# cpld.net
KiCad netlist of a schematic drawn in Altium Designer
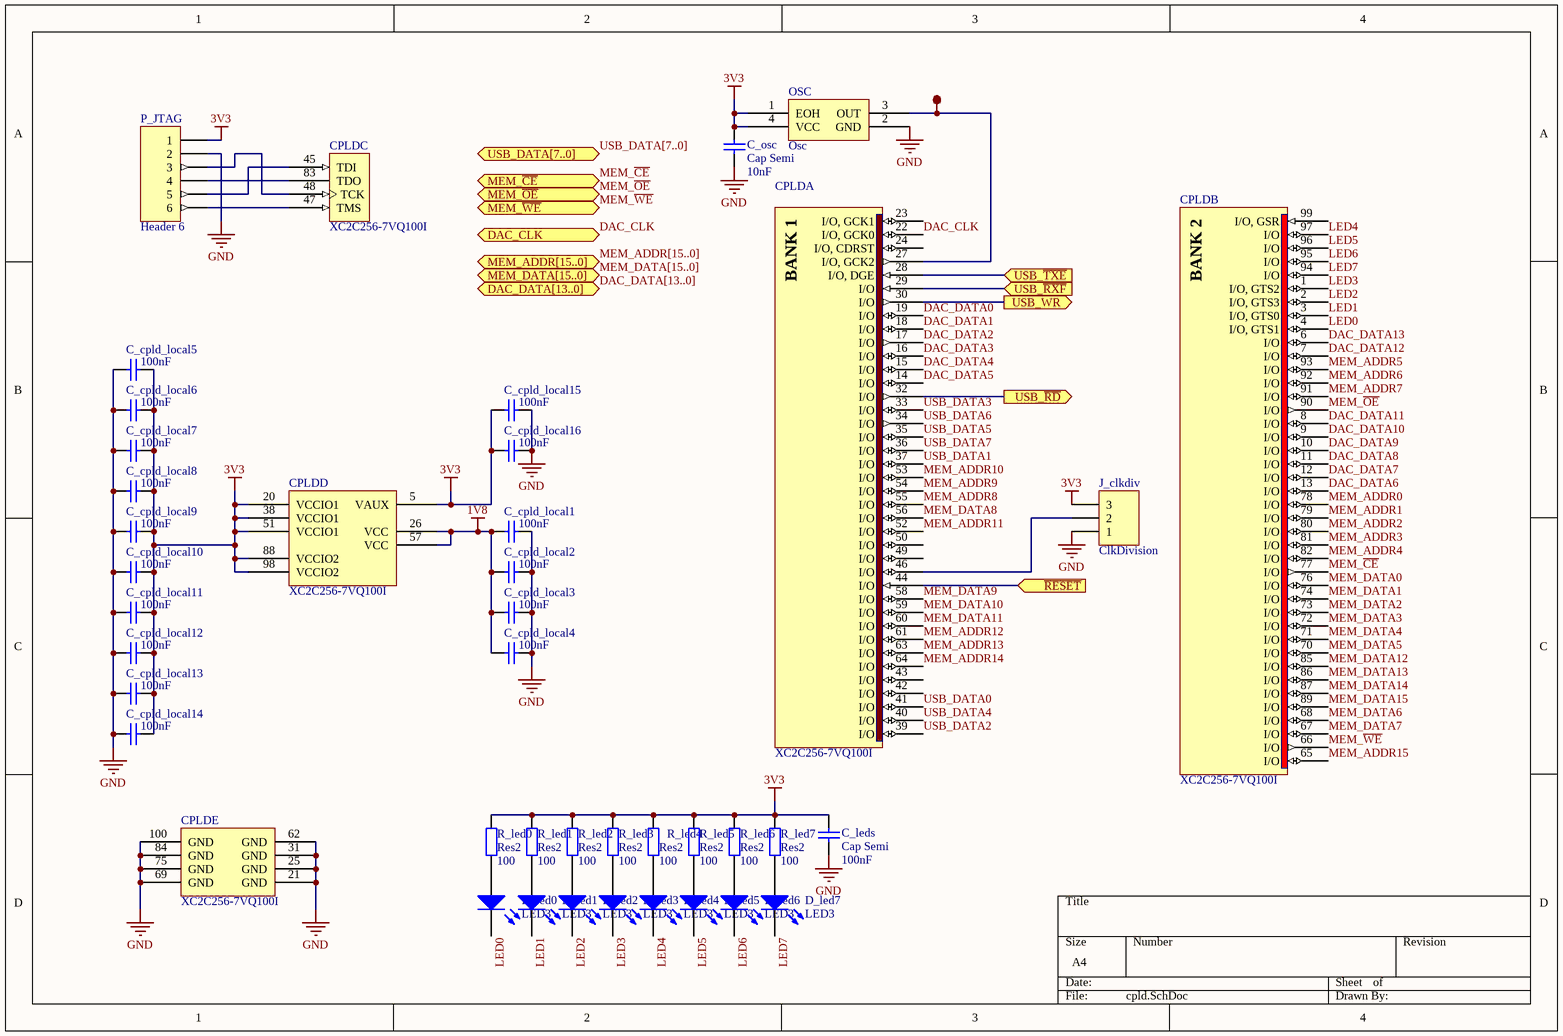
[diagram p0: cpld.SchDoc]

(export (version "E")
  (design (tool "Eeschema 10.0.6"))
  (components
    (comp (ref "CPLD")
      (value "XC2C256-7VQ100I")
      (footprint "VQ100_N")
      (description "CoolRunner-II 1.8V, 256 Macrocell CPLD, 80 User I/Os, 100-Pin VQFP, Industrial Grade")
      (fields (field (name "PUBLISHER") "Altium Limited"))
      (libsource (lib "Xilinx CoolRunner II") (part "XC2C256-7VQ100I"))
    )
    (comp (ref "C_cpld_local1")
      (value "100nF")
      (footprint "ourprints:0805")
      (description "Capacitor (Semiconductor SIM Model)")
      (fields (field (name "Comment") "Cap Semi") (field (name "PUBLISHER") "Altium Limited"))
      (libsource (lib "Miscellaneous Devices") (part "Cap Semi"))
    )
    (comp (ref "C_cpld_local2")
      (value "100nF")
      (footprint "ourprints:0805")
      (description "Capacitor (Semiconductor SIM Model)")
      (fields (field (name "Comment") "Cap Semi") (field (name "PUBLISHER") "Altium Limited"))
      (libsource (lib "Miscellaneous Devices") (part "Cap Semi"))
    )
    (comp (ref "C_cpld_local3")
      (value "100nF")
      (footprint "ourprints:0805")
      (description "Capacitor (Semiconductor SIM Model)")
      (fields (field (name "Comment") "Cap Semi") (field (name "PUBLISHER") "Altium Limited"))
      (libsource (lib "Miscellaneous Devices") (part "Cap Semi"))
    )
    (comp (ref "C_cpld_local4")
      (value "100nF")
      (footprint "ourprints:0805")
      (description "Capacitor (Semiconductor SIM Model)")
      (fields (field (name "Comment") "Cap Semi") (field (name "PUBLISHER") "Altium Limited"))
      (libsource (lib "Miscellaneous Devices") (part "Cap Semi"))
    )
    (comp (ref "C_cpld_local5")
      (value "100nF")
      (footprint "ourprints:0805")
      (description "Capacitor (Semiconductor SIM Model)")
      (fields (field (name "Comment") "Cap Semi") (field (name "PUBLISHER") "Altium Limited"))
      (libsource (lib "Miscellaneous Devices") (part "Cap Semi"))
    )
    (comp (ref "C_cpld_local6")
      (value "100nF")
      (footprint "ourprints:0805")
      (description "Capacitor (Semiconductor SIM Model)")
      (fields (field (name "Comment") "Cap Semi") (field (name "PUBLISHER") "Altium Limited"))
      (libsource (lib "Miscellaneous Devices") (part "Cap Semi"))
    )
    (comp (ref "C_cpld_local7")
      (value "100nF")
      (footprint "ourprints:0805")
      (description "Capacitor (Semiconductor SIM Model)")
      (fields (field (name "Comment") "Cap Semi") (field (name "PUBLISHER") "Altium Limited"))
      (libsource (lib "Miscellaneous Devices") (part "Cap Semi"))
    )
    (comp (ref "C_cpld_local8")
      (value "100nF")
      (footprint "ourprints:0805")
      (description "Capacitor (Semiconductor SIM Model)")
      (fields (field (name "Comment") "Cap Semi") (field (name "PUBLISHER") "Altium Limited"))
      (libsource (lib "Miscellaneous Devices") (part "Cap Semi"))
    )
    (comp (ref "C_cpld_local9")
      (value "100nF")
      (footprint "ourprints:0805")
      (description "Capacitor (Semiconductor SIM Model)")
      (fields (field (name "Comment") "Cap Semi") (field (name "PUBLISHER") "Altium Limited"))
      (libsource (lib "Miscellaneous Devices") (part "Cap Semi"))
    )
    (comp (ref "C_cpld_local10")
      (value "100nF")
      (footprint "ourprints:0805")
      (description "Capacitor (Semiconductor SIM Model)")
      (fields (field (name "Comment") "Cap Semi") (field (name "PUBLISHER") "Altium Limited"))
      (libsource (lib "Miscellaneous Devices") (part "Cap Semi"))
    )
    (comp (ref "C_cpld_local11")
      (value "100nF")
      (footprint "ourprints:0805")
      (description "Capacitor (Semiconductor SIM Model)")
      (fields (field (name "Comment") "Cap Semi") (field (name "PUBLISHER") "Altium Limited"))
      (libsource (lib "Miscellaneous Devices") (part "Cap Semi"))
    )
    (comp (ref "C_cpld_local12")
      (value "100nF")
      (footprint "ourprints:0805")
      (description "Capacitor (Semiconductor SIM Model)")
      (fields (field (name "Comment") "Cap Semi") (field (name "PUBLISHER") "Altium Limited"))
      (libsource (lib "Miscellaneous Devices") (part "Cap Semi"))
    )
    (comp (ref "C_cpld_local13")
      (value "100nF")
      (footprint "ourprints:0805")
      (description "Capacitor (Semiconductor SIM Model)")
      (fields (field (name "Comment") "Cap Semi") (field (name "PUBLISHER") "Altium Limited"))
      (libsource (lib "Miscellaneous Devices") (part "Cap Semi"))
    )
    (comp (ref "C_cpld_local14")
      (value "100nF")
      (footprint "ourprints:0805")
      (description "Capacitor (Semiconductor SIM Model)")
      (fields (field (name "Comment") "Cap Semi") (field (name "PUBLISHER") "Altium Limited"))
      (libsource (lib "Miscellaneous Devices") (part "Cap Semi"))
    )
    (comp (ref "C_cpld_local15")
      (value "100nF")
      (footprint "ourprints:0805")
      (description "Capacitor (Semiconductor SIM Model)")
      (fields (field (name "Comment") "Cap Semi") (field (name "PUBLISHER") "Altium Limited"))
      (libsource (lib "Miscellaneous Devices") (part "Cap Semi"))
    )
    (comp (ref "C_cpld_local16")
      (value "100nF")
      (footprint "ourprints:0805")
      (description "Capacitor (Semiconductor SIM Model)")
      (fields (field (name "Comment") "Cap Semi") (field (name "PUBLISHER") "Altium Limited"))
      (libsource (lib "Miscellaneous Devices") (part "Cap Semi"))
    )
    (comp (ref "C_leds")
      (value "Cap Semi")
      (footprint "ourprints:0805")
      (description "Capacitor (Semiconductor SIM Model)")
      (fields (field (name "ALTIUM_VALUE") "100nF") (field (name "PUBLISHER") "Altium Limited"))
      (libsource (lib "Miscellaneous Devices") (part "Cap Semi"))
    )
    (comp (ref "C_osc")
      (value "Cap Semi")
      (footprint "ourprints:0805")
      (description "Capacitor (Semiconductor SIM Model)")
      (fields (field (name "ALTIUM_VALUE") "10nF") (field (name "PUBLISHER") "Altium Limited"))
      (libsource (lib "Miscellaneous Devices") (part "Cap Semi"))
    )
    (comp (ref "D_led0")
      (value "LED3")
      (footprint "ourprints:0805")
      (description "Typical BLUE SiC LED")
      (fields (field (name "PUBLISHER") "Altium Limited"))
      (libsource (lib "Miscellaneous Devices") (part "LED3"))
    )
    (comp (ref "D_led1")
      (value "LED3")
      (footprint "ourprints:0805")
      (description "Typical BLUE SiC LED")
      (fields (field (name "PUBLISHER") "Altium Limited"))
      (libsource (lib "Miscellaneous Devices") (part "LED3"))
    )
    (comp (ref "D_led2")
      (value "LED3")
      (footprint "ourprints:0805")
      (description "Typical BLUE SiC LED")
      (fields (field (name "PUBLISHER") "Altium Limited"))
      (libsource (lib "Miscellaneous Devices") (part "LED3"))
    )
    (comp (ref "D_led3")
      (value "LED3")
      (footprint "ourprints:0805")
      (description "Typical BLUE SiC LED")
      (fields (field (name "PUBLISHER") "Altium Limited"))
      (libsource (lib "Miscellaneous Devices") (part "LED3"))
    )
    (comp (ref "D_led4")
      (value "LED3")
      (footprint "ourprints:0805")
      (description "Typical BLUE SiC LED")
      (fields (field (name "PUBLISHER") "Altium Limited"))
      (libsource (lib "Miscellaneous Devices") (part "LED3"))
    )
    (comp (ref "D_led5")
      (value "LED3")
      (footprint "ourprints:0805")
      (description "Typical BLUE SiC LED")
      (fields (field (name "PUBLISHER") "Altium Limited"))
      (libsource (lib "Miscellaneous Devices") (part "LED3"))
    )
    (comp (ref "D_led6")
      (value "LED3")
      (footprint "ourprints:0805")
      (description "Typical BLUE SiC LED")
      (fields (field (name "PUBLISHER") "Altium Limited"))
      (libsource (lib "Miscellaneous Devices") (part "LED3"))
    )
    (comp (ref "D_led7")
      (value "LED3")
      (footprint "ourprints:0805")
      (description "Typical BLUE SiC LED")
      (fields (field (name "PUBLISHER") "Altium Limited"))
      (libsource (lib "Miscellaneous Devices") (part "LED3"))
    )
    (comp (ref "J_clkdiv")
      (value "ClkDivision")
      (footprint "HDR1X3")
      (description "Header, 3-Pin")
      (fields (field (name "PUBLISHER") "Altium Limited"))
      (libsource (lib "Miscellaneous Connectors") (part "Header 3"))
    )
    (comp (ref "OSC") (value "Osc") (footprint "OSC") (libsource (lib "ourlibs") (part "Osc")))
    (comp (ref "P_JTAG")
      (value "Header 6")
      (footprint "HDR1X6")
      (description "Header, 6-Pin")
      (fields (field (name "PUBLISHER") "Altium Limited"))
      (libsource (lib "Miscellaneous Connectors") (part "Header 6"))
    )
    (comp (ref "R_led0")
      (value "Res2")
      (footprint "ourprints:0805")
      (description "Resistor")
      (fields (field (name "ALTIUM_VALUE") "100") (field (name "PUBLISHER") "Altium Limited"))
      (libsource (lib "Miscellaneous Devices") (part "Res2"))
    )
    (comp (ref "R_led1")
      (value "Res2")
      (footprint "ourprints:0805")
      (description "Resistor")
      (fields (field (name "ALTIUM_VALUE") "100") (field (name "PUBLISHER") "Altium Limited"))
      (libsource (lib "Miscellaneous Devices") (part "Res2"))
    )
    (comp (ref "R_led2")
      (value "Res2")
      (footprint "ourprints:0805")
      (description "Resistor")
      (fields (field (name "ALTIUM_VALUE") "100") (field (name "PUBLISHER") "Altium Limited"))
      (libsource (lib "Miscellaneous Devices") (part "Res2"))
    )
    (comp (ref "R_led3")
      (value "Res2")
      (footprint "ourprints:0805")
      (description "Resistor")
      (fields (field (name "ALTIUM_VALUE") "100") (field (name "PUBLISHER") "Altium Limited"))
      (libsource (lib "Miscellaneous Devices") (part "Res2"))
    )
    (comp (ref "R_led4")
      (value "Res2")
      (footprint "ourprints:0805")
      (description "Resistor")
      (fields (field (name "ALTIUM_VALUE") "100") (field (name "PUBLISHER") "Altium Limited"))
      (libsource (lib "Miscellaneous Devices") (part "Res2"))
    )
    (comp (ref "R_led5")
      (value "Res2")
      (footprint "ourprints:0805")
      (description "Resistor")
      (fields (field (name "ALTIUM_VALUE") "100") (field (name "PUBLISHER") "Altium Limited"))
      (libsource (lib "Miscellaneous Devices") (part "Res2"))
    )
    (comp (ref "R_led6")
      (value "Res2")
      (footprint "ourprints:0805")
      (description "Resistor")
      (fields (field (name "ALTIUM_VALUE") "100") (field (name "PUBLISHER") "Altium Limited"))
      (libsource (lib "Miscellaneous Devices") (part "Res2"))
    )
    (comp (ref "R_led7")
      (value "Res2")
      (footprint "ourprints:0805")
      (description "Resistor")
      (fields (field (name "ALTIUM_VALUE") "100") (field (name "PUBLISHER") "Altium Limited"))
      (libsource (lib "Miscellaneous Devices") (part "Res2"))
    )
    (comp (ref "TP_osc")
      (value "TestPoint")
      (footprint "testpoint")
      (libsource (lib "ourlibs") (part "TestPoint"))
    )
  )
  (nets
    (net (code "1") (name "/DAC_CLK") (class "Default")
      (node (ref "CPLD") (pin "22") (pinfunction "I/O,_GCK0_22") (pintype "bidirectional"))
    )
    (net (code "2") (name "/DAC_DATA0") (class "Default")
      (node (ref "CPLD") (pin "19") (pinfunction "I/O_19") (pintype "bidirectional"))
    )
    (net (code "3") (name "/DAC_DATA1") (class "Default")
      (node (ref "CPLD") (pin "18") (pinfunction "I/O_18") (pintype "bidirectional"))
    )
    (net (code "4") (name "/DAC_DATA2") (class "Default")
      (node (ref "CPLD") (pin "17") (pinfunction "I/O_17") (pintype "bidirectional"))
    )
    (net (code "5") (name "/DAC_DATA3") (class "Default")
      (node (ref "CPLD") (pin "16") (pinfunction "I/O_16") (pintype "bidirectional"))
    )
    (net (code "6") (name "/DAC_DATA4") (class "Default")
      (node (ref "CPLD") (pin "15") (pinfunction "I/O_15") (pintype "bidirectional"))
    )
    (net (code "7") (name "/DAC_DATA5") (class "Default")
      (node (ref "CPLD") (pin "14") (pinfunction "I/O_14") (pintype "bidirectional"))
    )
    (net (code "8") (name "/DAC_DATA6") (class "Default")
      (node (ref "CPLD") (pin "13") (pinfunction "I/O_13") (pintype "bidirectional"))
    )
    (net (code "9") (name "/DAC_DATA7") (class "Default")
      (node (ref "CPLD") (pin "12") (pinfunction "I/O_12") (pintype "bidirectional"))
    )
    (net (code "10") (name "/DAC_DATA8") (class "Default")
      (node (ref "CPLD") (pin "11") (pinfunction "I/O_11") (pintype "bidirectional"))
    )
    (net (code "11") (name "/DAC_DATA9") (class "Default")
      (node (ref "CPLD") (pin "10") (pinfunction "I/O_10") (pintype "bidirectional"))
    )
    (net (code "12") (name "/DAC_DATA10") (class "Default")
      (node (ref "CPLD") (pin "9") (pinfunction "I/O_9") (pintype "bidirectional"))
    )
    (net (code "13") (name "/DAC_DATA11") (class "Default")
      (node (ref "CPLD") (pin "8") (pinfunction "I/O_8") (pintype "bidirectional"))
    )
    (net (code "14") (name "/DAC_DATA12") (class "Default")
      (node (ref "CPLD") (pin "7") (pinfunction "I/O_7") (pintype "bidirectional"))
    )
    (net (code "15") (name "/DAC_DATA13") (class "Default")
      (node (ref "CPLD") (pin "6") (pinfunction "I/O_6") (pintype "bidirectional"))
    )
    (net (code "17") (name "/LED0") (class "Default")
      (node (ref "CPLD") (pin "4") (pinfunction "I/O,_GTS1_4") (pintype "bidirectional"))
      (node (ref "D_led0") (pin "2") (pinfunction "K_2") (pintype "passive"))
    )
    (net (code "18") (name "/LED1") (class "Default")
      (node (ref "CPLD") (pin "3") (pinfunction "I/O,_GTS0_3") (pintype "bidirectional"))
      (node (ref "D_led1") (pin "2") (pinfunction "K_2") (pintype "passive"))
    )
    (net (code "19") (name "/LED2") (class "Default")
      (node (ref "CPLD") (pin "2") (pinfunction "I/O,_GTS3_2") (pintype "bidirectional"))
      (node (ref "D_led2") (pin "2") (pinfunction "K_2") (pintype "passive"))
    )
    (net (code "20") (name "/LED3") (class "Default")
      (node (ref "CPLD") (pin "1") (pinfunction "I/O,_GTS2_1") (pintype "bidirectional"))
      (node (ref "D_led3") (pin "2") (pinfunction "K_2") (pintype "passive"))
    )
    (net (code "21") (name "/LED4") (class "Default")
      (node (ref "CPLD") (pin "97") (pinfunction "I/O_97") (pintype "bidirectional"))
      (node (ref "D_led4") (pin "2") (pinfunction "K_2") (pintype "passive"))
    )
    (net (code "22") (name "/LED5") (class "Default")
      (node (ref "CPLD") (pin "96") (pinfunction "I/O_96") (pintype "bidirectional"))
      (node (ref "D_led5") (pin "2") (pinfunction "K_2") (pintype "passive"))
    )
    (net (code "23") (name "/LED6") (class "Default")
      (node (ref "CPLD") (pin "95") (pinfunction "I/O_95") (pintype "bidirectional"))
      (node (ref "D_led6") (pin "2") (pinfunction "K_2") (pintype "passive"))
    )
    (net (code "24") (name "/LED7") (class "Default")
      (node (ref "CPLD") (pin "94") (pinfunction "I/O_94") (pintype "bidirectional"))
      (node (ref "D_led7") (pin "2") (pinfunction "K_2") (pintype "passive"))
    )
    (net (code "25") (name "/MEM_ADDR0") (class "Default")
      (node (ref "CPLD") (pin "78") (pinfunction "I/O_78") (pintype "bidirectional"))
    )
    (net (code "26") (name "/MEM_ADDR1") (class "Default")
      (node (ref "CPLD") (pin "79") (pinfunction "I/O_79") (pintype "bidirectional"))
    )
    (net (code "27") (name "/MEM_ADDR2") (class "Default")
      (node (ref "CPLD") (pin "80") (pinfunction "I/O_80") (pintype "bidirectional"))
    )
    (net (code "28") (name "/MEM_ADDR3") (class "Default")
      (node (ref "CPLD") (pin "81") (pinfunction "I/O_81") (pintype "bidirectional"))
    )
    (net (code "29") (name "/MEM_ADDR4") (class "Default")
      (node (ref "CPLD") (pin "82") (pinfunction "I/O_82") (pintype "bidirectional"))
    )
    (net (code "30") (name "/MEM_ADDR5") (class "Default")
      (node (ref "CPLD") (pin "93") (pinfunction "I/O_93") (pintype "bidirectional"))
    )
    (net (code "31") (name "/MEM_ADDR6") (class "Default")
      (node (ref "CPLD") (pin "92") (pinfunction "I/O_92") (pintype "bidirectional"))
    )
    (net (code "32") (name "/MEM_ADDR7") (class "Default")
      (node (ref "CPLD") (pin "91") (pinfunction "I/O_91") (pintype "bidirectional"))
    )
    (net (code "33") (name "/MEM_ADDR8") (class "Default")
      (node (ref "CPLD") (pin "55") (pinfunction "I/O_55") (pintype "bidirectional"))
    )
    (net (code "34") (name "/MEM_ADDR9") (class "Default")
      (node (ref "CPLD") (pin "54") (pinfunction "I/O_54") (pintype "bidirectional"))
    )
    (net (code "35") (name "/MEM_ADDR10") (class "Default")
      (node (ref "CPLD") (pin "53") (pinfunction "I/O_53") (pintype "bidirectional"))
    )
    (net (code "36") (name "/MEM_ADDR11") (class "Default")
      (node (ref "CPLD") (pin "52") (pinfunction "I/O_52") (pintype "bidirectional"))
    )
    (net (code "37") (name "/MEM_ADDR12") (class "Default")
      (node (ref "CPLD") (pin "61") (pinfunction "I/O_61") (pintype "bidirectional"))
    )
    (net (code "38") (name "/MEM_ADDR13") (class "Default")
      (node (ref "CPLD") (pin "63") (pinfunction "I/O_63") (pintype "bidirectional"))
    )
    (net (code "39") (name "/MEM_ADDR14") (class "Default")
      (node (ref "CPLD") (pin "64") (pinfunction "I/O_64") (pintype "bidirectional"))
    )
    (net (code "40") (name "/MEM_ADDR15") (class "Default")
      (node (ref "CPLD") (pin "65") (pinfunction "I/O_65") (pintype "bidirectional"))
    )
    (net (code "42") (name "/MEM_DATA0") (class "Default")
      (node (ref "CPLD") (pin "76") (pinfunction "I/O_76") (pintype "bidirectional"))
    )
    (net (code "43") (name "/MEM_DATA1") (class "Default")
      (node (ref "CPLD") (pin "74") (pinfunction "I/O_74") (pintype "bidirectional"))
    )
    (net (code "44") (name "/MEM_DATA2") (class "Default")
      (node (ref "CPLD") (pin "73") (pinfunction "I/O_73") (pintype "bidirectional"))
    )
    (net (code "45") (name "/MEM_DATA3") (class "Default")
      (node (ref "CPLD") (pin "72") (pinfunction "I/O_72") (pintype "bidirectional"))
    )
    (net (code "46") (name "/MEM_DATA4") (class "Default")
      (node (ref "CPLD") (pin "71") (pinfunction "I/O_71") (pintype "bidirectional"))
    )
    (net (code "47") (name "/MEM_DATA5") (class "Default")
      (node (ref "CPLD") (pin "70") (pinfunction "I/O_70") (pintype "bidirectional"))
    )
    (net (code "48") (name "/MEM_DATA6") (class "Default")
      (node (ref "CPLD") (pin "68") (pinfunction "I/O_68") (pintype "bidirectional"))
    )
    (net (code "49") (name "/MEM_DATA7") (class "Default")
      (node (ref "CPLD") (pin "67") (pinfunction "I/O_67") (pintype "bidirectional"))
    )
    (net (code "50") (name "/MEM_DATA8") (class "Default")
      (node (ref "CPLD") (pin "56") (pinfunction "I/O_56") (pintype "bidirectional"))
    )
    (net (code "51") (name "/MEM_DATA9") (class "Default")
      (node (ref "CPLD") (pin "58") (pinfunction "I/O_58") (pintype "bidirectional"))
    )
    (net (code "52") (name "/MEM_DATA10") (class "Default")
      (node (ref "CPLD") (pin "59") (pinfunction "I/O_59") (pintype "bidirectional"))
    )
    (net (code "53") (name "/MEM_DATA11") (class "Default")
      (node (ref "CPLD") (pin "60") (pinfunction "I/O_60") (pintype "bidirectional"))
    )
    (net (code "54") (name "/MEM_DATA12") (class "Default")
      (node (ref "CPLD") (pin "85") (pinfunction "I/O_85") (pintype "bidirectional"))
    )
    (net (code "55") (name "/MEM_DATA13") (class "Default")
      (node (ref "CPLD") (pin "86") (pinfunction "I/O_86") (pintype "bidirectional"))
    )
    (net (code "56") (name "/MEM_DATA14") (class "Default")
      (node (ref "CPLD") (pin "87") (pinfunction "I/O_87") (pintype "bidirectional"))
    )
    (net (code "57") (name "/MEM_DATA15") (class "Default")
      (node (ref "CPLD") (pin "89") (pinfunction "I/O_89") (pintype "bidirectional"))
    )
    (net (code "59") (name "/MEM_~{CE}") (class "Default")
      (node (ref "CPLD") (pin "77") (pinfunction "I/O_77") (pintype "bidirectional"))
    )
    (net (code "60") (name "/MEM_~{OE}") (class "Default")
      (node (ref "CPLD") (pin "90") (pinfunction "I/O_90") (pintype "bidirectional"))
    )
    (net (code "61") (name "/MEM_~{WE}") (class "Default")
      (node (ref "CPLD") (pin "66") (pinfunction "I/O_66") (pintype "bidirectional"))
    )
    (net (code "62") (name "/USB_DATA0") (class "Default")
      (node (ref "CPLD") (pin "41") (pinfunction "I/O_41") (pintype "bidirectional"))
    )
    (net (code "63") (name "/USB_DATA1") (class "Default")
      (node (ref "CPLD") (pin "37") (pinfunction "I/O_37") (pintype "bidirectional"))
    )
    (net (code "64") (name "/USB_DATA2") (class "Default")
      (node (ref "CPLD") (pin "39") (pinfunction "I/O_39") (pintype "bidirectional"))
    )
    (net (code "65") (name "/USB_DATA3") (class "Default")
      (node (ref "CPLD") (pin "33") (pinfunction "I/O_33") (pintype "bidirectional"))
    )
    (net (code "66") (name "/USB_DATA4") (class "Default")
      (node (ref "CPLD") (pin "40") (pinfunction "I/O_40") (pintype "bidirectional"))
    )
    (net (code "67") (name "/USB_DATA5") (class "Default")
      (node (ref "CPLD") (pin "35") (pinfunction "I/O_35") (pintype "bidirectional"))
    )
    (net (code "68") (name "/USB_DATA6") (class "Default")
      (node (ref "CPLD") (pin "34") (pinfunction "I/O_34") (pintype "bidirectional"))
    )
    (net (code "69") (name "/USB_DATA7") (class "Default")
      (node (ref "CPLD") (pin "36") (pinfunction "I/O_36") (pintype "bidirectional"))
    )
    (net (code "71") (name "/USB_WR") (class "Default")
      (node (ref "CPLD") (pin "30") (pinfunction "I/O_30") (pintype "bidirectional"))
    )
    (net (code "72") (name "/USB_~{RD}") (class "Default")
      (node (ref "CPLD") (pin "32") (pinfunction "I/O_32") (pintype "bidirectional"))
    )
    (net (code "73") (name "/USB_~{RXF}") (class "Default")
      (node (ref "CPLD") (pin "29") (pinfunction "I/O_29") (pintype "bidirectional"))
    )
    (net (code "74") (name "/USB_~{TXE}") (class "Default")
      (node (ref "CPLD") (pin "28") (pinfunction "I/O,_DGE_28") (pintype "bidirectional"))
    )
    (net (code "75") (name "/~{RESET}") (class "Default")
      (node (ref "CPLD") (pin "44") (pinfunction "I/O_44") (pintype "bidirectional"))
    )
    (net (code "76") (name "1V8") (class "Default")
      (node (ref "CPLD") (pin "26") (pinfunction "VCC_26") (pintype "power_in"))
      (node (ref "CPLD") (pin "57") (pinfunction "VCC_57") (pintype "power_in"))
      (node (ref "C_cpld_local1") (pin "2") (pinfunction "2_2") (pintype "passive"))
      (node (ref "C_cpld_local2") (pin "2") (pinfunction "2_2") (pintype "passive"))
      (node (ref "C_cpld_local3") (pin "2") (pinfunction "2_2") (pintype "passive"))
      (node (ref "C_cpld_local4") (pin "2") (pinfunction "2_2") (pintype "passive"))
    )
    (net (code "77") (name "3V3") (class "Default")
      (node (ref "CPLD") (pin "20") (pinfunction "VCCIO1_20") (pintype "power_in"))
      (node (ref "CPLD") (pin "38") (pinfunction "VCCIO1_38") (pintype "power_in"))
      (node (ref "CPLD") (pin "5") (pinfunction "VAUX_5") (pintype "power_in"))
      (node (ref "CPLD") (pin "51") (pinfunction "VCCIO1_51") (pintype "power_in"))
      (node (ref "CPLD") (pin "88") (pinfunction "VCCIO2_88") (pintype "power_in"))
      (node (ref "CPLD") (pin "98") (pinfunction "VCCIO2_98") (pintype "power_in"))
      (node (ref "C_cpld_local10") (pin "1") (pinfunction "1_1") (pintype "passive"))
      (node (ref "C_cpld_local11") (pin "1") (pinfunction "1_1") (pintype "passive"))
      (node (ref "C_cpld_local12") (pin "1") (pinfunction "1_1") (pintype "passive"))
      (node (ref "C_cpld_local13") (pin "1") (pinfunction "1_1") (pintype "passive"))
      (node (ref "C_cpld_local14") (pin "1") (pinfunction "1_1") (pintype "passive"))
      (node (ref "C_cpld_local15") (pin "2") (pinfunction "2_2") (pintype "passive"))
      (node (ref "C_cpld_local16") (pin "2") (pinfunction "2_2") (pintype "passive"))
      (node (ref "C_cpld_local5") (pin "1") (pinfunction "1_1") (pintype "passive"))
      (node (ref "C_cpld_local6") (pin "1") (pinfunction "1_1") (pintype "passive"))
      (node (ref "C_cpld_local7") (pin "1") (pinfunction "1_1") (pintype "passive"))
      (node (ref "C_cpld_local8") (pin "1") (pinfunction "1_1") (pintype "passive"))
      (node (ref "C_cpld_local9") (pin "1") (pinfunction "1_1") (pintype "passive"))
      (node (ref "C_leds") (pin "2") (pinfunction "2_2") (pintype "passive"))
      (node (ref "C_osc") (pin "2") (pinfunction "2_2") (pintype "passive"))
      (node (ref "J_clkdiv") (pin "3") (pinfunction "3_3") (pintype "passive"))
      (node (ref "OSC") (pin "1") (pinfunction "EOH_1") (pintype "passive"))
      (node (ref "OSC") (pin "4") (pinfunction "VCC_4") (pintype "passive"))
      (node (ref "P_JTAG") (pin "1") (pinfunction "1_1") (pintype "passive"))
      (node (ref "R_led0") (pin "2") (pinfunction "2_2") (pintype "passive"))
      (node (ref "R_led1") (pin "2") (pinfunction "2_2") (pintype "passive"))
      (node (ref "R_led2") (pin "2") (pinfunction "2_2") (pintype "passive"))
      (node (ref "R_led3") (pin "2") (pinfunction "2_2") (pintype "passive"))
      (node (ref "R_led4") (pin "2") (pinfunction "2_2") (pintype "passive"))
      (node (ref "R_led5") (pin "2") (pinfunction "2_2") (pintype "passive"))
      (node (ref "R_led6") (pin "2") (pinfunction "2_2") (pintype "passive"))
      (node (ref "R_led7") (pin "2") (pinfunction "2_2") (pintype "passive"))
    )
    (net (code "78") (name "GND") (class "Default")
      (node (ref "CPLD") (pin "100") (pinfunction "GND_100") (pintype "power_in"))
      (node (ref "CPLD") (pin "21") (pinfunction "GND_21") (pintype "power_in"))
      (node (ref "CPLD") (pin "25") (pinfunction "GND_25") (pintype "power_in"))
      (node (ref "CPLD") (pin "31") (pinfunction "GND_31") (pintype "power_in"))
      (node (ref "CPLD") (pin "62") (pinfunction "GND_62") (pintype "power_in"))
      (node (ref "CPLD") (pin "69") (pinfunction "GND_69") (pintype "power_in"))
      (node (ref "CPLD") (pin "75") (pinfunction "GND_75") (pintype "power_in"))
      (node (ref "CPLD") (pin "84") (pinfunction "GND_84") (pintype "power_in"))
      (node (ref "C_cpld_local1") (pin "1") (pinfunction "1_1") (pintype "passive"))
      (node (ref "C_cpld_local10") (pin "2") (pinfunction "2_2") (pintype "passive"))
      (node (ref "C_cpld_local11") (pin "2") (pinfunction "2_2") (pintype "passive"))
      (node (ref "C_cpld_local12") (pin "2") (pinfunction "2_2") (pintype "passive"))
      (node (ref "C_cpld_local13") (pin "2") (pinfunction "2_2") (pintype "passive"))
      (node (ref "C_cpld_local14") (pin "2") (pinfunction "2_2") (pintype "passive"))
      (node (ref "C_cpld_local15") (pin "1") (pinfunction "1_1") (pintype "passive"))
      (node (ref "C_cpld_local16") (pin "1") (pinfunction "1_1") (pintype "passive"))
      (node (ref "C_cpld_local2") (pin "1") (pinfunction "1_1") (pintype "passive"))
      (node (ref "C_cpld_local3") (pin "1") (pinfunction "1_1") (pintype "passive"))
      (node (ref "C_cpld_local4") (pin "1") (pinfunction "1_1") (pintype "passive"))
      (node (ref "C_cpld_local5") (pin "2") (pinfunction "2_2") (pintype "passive"))
      (node (ref "C_cpld_local6") (pin "2") (pinfunction "2_2") (pintype "passive"))
      (node (ref "C_cpld_local7") (pin "2") (pinfunction "2_2") (pintype "passive"))
      (node (ref "C_cpld_local8") (pin "2") (pinfunction "2_2") (pintype "passive"))
      (node (ref "C_cpld_local9") (pin "2") (pinfunction "2_2") (pintype "passive"))
      (node (ref "C_leds") (pin "1") (pinfunction "1_1") (pintype "passive"))
      (node (ref "C_osc") (pin "1") (pinfunction "1_1") (pintype "passive"))
      (node (ref "J_clkdiv") (pin "1") (pinfunction "1_1") (pintype "passive"))
      (node (ref "OSC") (pin "2") (pinfunction "GND_2") (pintype "passive"))
      (node (ref "P_JTAG") (pin "2") (pinfunction "2_2") (pintype "passive"))
    )
    (net (code "79") (name "Net-(CPLDA-I{slash}O,_GCK2)") (class "Default")
      (node (ref "CPLD") (pin "27") (pinfunction "I/O,_GCK2_27") (pintype "bidirectional"))
      (node (ref "OSC") (pin "3") (pinfunction "OUT_3") (pintype "passive"))
      (node (ref "TP_osc") (pin "1") (pinfunction "TP_1") (pintype "passive"))
    )
    (net (code "80") (name "Net-(CPLDA-I{slash}O-Pad46)") (class "Default")
      (node (ref "CPLD") (pin "46") (pinfunction "I/O_46") (pintype "bidirectional"))
      (node (ref "J_clkdiv") (pin "2") (pinfunction "2_2") (pintype "passive"))
    )
    (net (code "81") (name "Net-(CPLDC-TCK)") (class "Default")
      (node (ref "CPLD") (pin "48") (pinfunction "TCK_48") (pintype "input"))
      (node (ref "P_JTAG") (pin "3") (pinfunction "3_3") (pintype "output"))
    )
    (net (code "82") (name "Net-(CPLDC-TDI)") (class "Default")
      (node (ref "CPLD") (pin "45") (pinfunction "TDI_45") (pintype "input"))
      (node (ref "P_JTAG") (pin "5") (pinfunction "5_5") (pintype "output"))
    )
    (net (code "83") (name "Net-(CPLDC-TDO)") (class "Default")
      (node (ref "CPLD") (pin "83") (pinfunction "TDO_83") (pintype "passive"))
      (node (ref "P_JTAG") (pin "4") (pinfunction "4_4") (pintype "passive"))
    )
    (net (code "84") (name "Net-(CPLDC-TMS)") (class "Default")
      (node (ref "CPLD") (pin "47") (pinfunction "TMS_47") (pintype "input"))
      (node (ref "P_JTAG") (pin "6") (pinfunction "6_6") (pintype "output"))
    )
    (net (code "85") (name "Net-(D_led0-A)") (class "Default")
      (node (ref "D_led0") (pin "1") (pinfunction "A_1") (pintype "passive"))
      (node (ref "R_led0") (pin "1") (pinfunction "1_1") (pintype "passive"))
    )
    (net (code "86") (name "Net-(D_led1-A)") (class "Default")
      (node (ref "D_led1") (pin "1") (pinfunction "A_1") (pintype "passive"))
      (node (ref "R_led1") (pin "1") (pinfunction "1_1") (pintype "passive"))
    )
    (net (code "87") (name "Net-(D_led2-A)") (class "Default")
      (node (ref "D_led2") (pin "1") (pinfunction "A_1") (pintype "passive"))
      (node (ref "R_led2") (pin "1") (pinfunction "1_1") (pintype "passive"))
    )
    (net (code "88") (name "Net-(D_led3-A)") (class "Default")
      (node (ref "D_led3") (pin "1") (pinfunction "A_1") (pintype "passive"))
      (node (ref "R_led3") (pin "1") (pinfunction "1_1") (pintype "passive"))
    )
    (net (code "89") (name "Net-(D_led4-A)") (class "Default")
      (node (ref "D_led4") (pin "1") (pinfunction "A_1") (pintype "passive"))
      (node (ref "R_led4") (pin "1") (pinfunction "1_1") (pintype "passive"))
    )
    (net (code "90") (name "Net-(D_led5-A)") (class "Default")
      (node (ref "D_led5") (pin "1") (pinfunction "A_1") (pintype "passive"))
      (node (ref "R_led5") (pin "1") (pinfunction "1_1") (pintype "passive"))
    )
    (net (code "91") (name "Net-(D_led6-A)") (class "Default")
      (node (ref "D_led6") (pin "1") (pinfunction "A_1") (pintype "passive"))
      (node (ref "R_led6") (pin "1") (pinfunction "1_1") (pintype "passive"))
    )
    (net (code "92") (name "Net-(D_led7-A)") (class "Default")
      (node (ref "D_led7") (pin "1") (pinfunction "A_1") (pintype "passive"))
      (node (ref "R_led7") (pin "1") (pinfunction "1_1") (pintype "passive"))
    )
    (net (code "93") (name "unconnected-(CPLDA-I{slash}O,_CDRST-Pad24)") (class "Default")
      (node (ref "CPLD") (pin "24") (pinfunction "I/O,_CDRST_24") (pintype "bidirectional"))
    )
    (net (code "94") (name "unconnected-(CPLDA-I{slash}O,_GCK1-Pad23)") (class "Default")
      (node (ref "CPLD") (pin "23") (pinfunction "I/O,_GCK1_23") (pintype "bidirectional"))
    )
    (net (code "95") (name "unconnected-(CPLDA-I{slash}O-Pad42)") (class "Default")
      (node (ref "CPLD") (pin "42") (pinfunction "I/O_42") (pintype "bidirectional"))
    )
    (net (code "96") (name "unconnected-(CPLDA-I{slash}O-Pad43)") (class "Default")
      (node (ref "CPLD") (pin "43") (pinfunction "I/O_43") (pintype "bidirectional"))
    )
    (net (code "97") (name "unconnected-(CPLDA-I{slash}O-Pad49)") (class "Default")
      (node (ref "CPLD") (pin "49") (pinfunction "I/O_49") (pintype "bidirectional"))
    )
    (net (code "98") (name "unconnected-(CPLDA-I{slash}O-Pad50)") (class "Default")
      (node (ref "CPLD") (pin "50") (pinfunction "I/O_50") (pintype "bidirectional"))
    )
    (net (code "99") (name "unconnected-(CPLDB-I{slash}O,_GSR-Pad99)") (class "Default")
      (node (ref "CPLD") (pin "99") (pinfunction "I/O,_GSR_99") (pintype "bidirectional"))
    )
  )
)
